# IO4-SignalDriver-Small.net
KiCad netlist of a schematic drawn in EAGLE
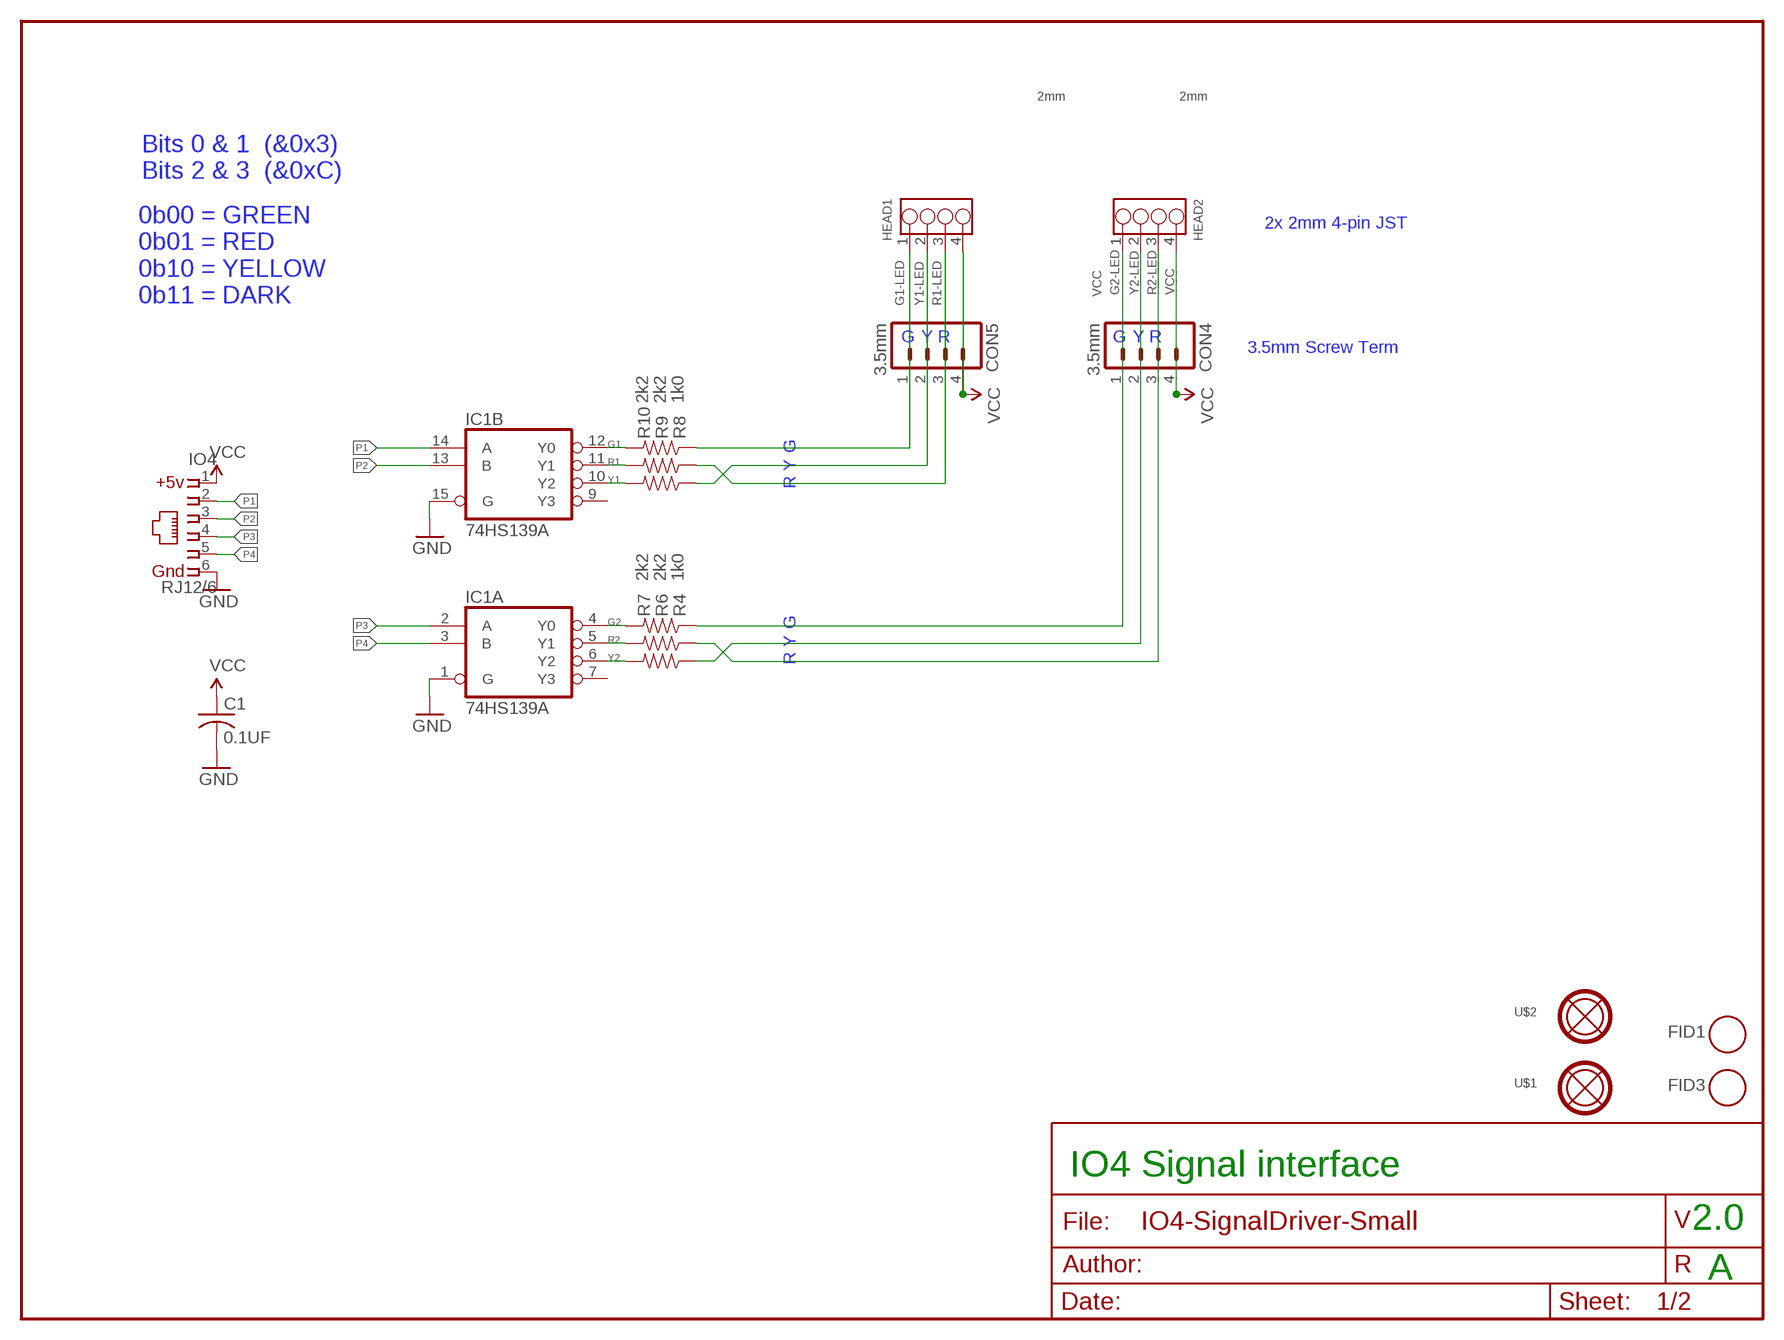
[diagram p0: schematic, sheet 1]
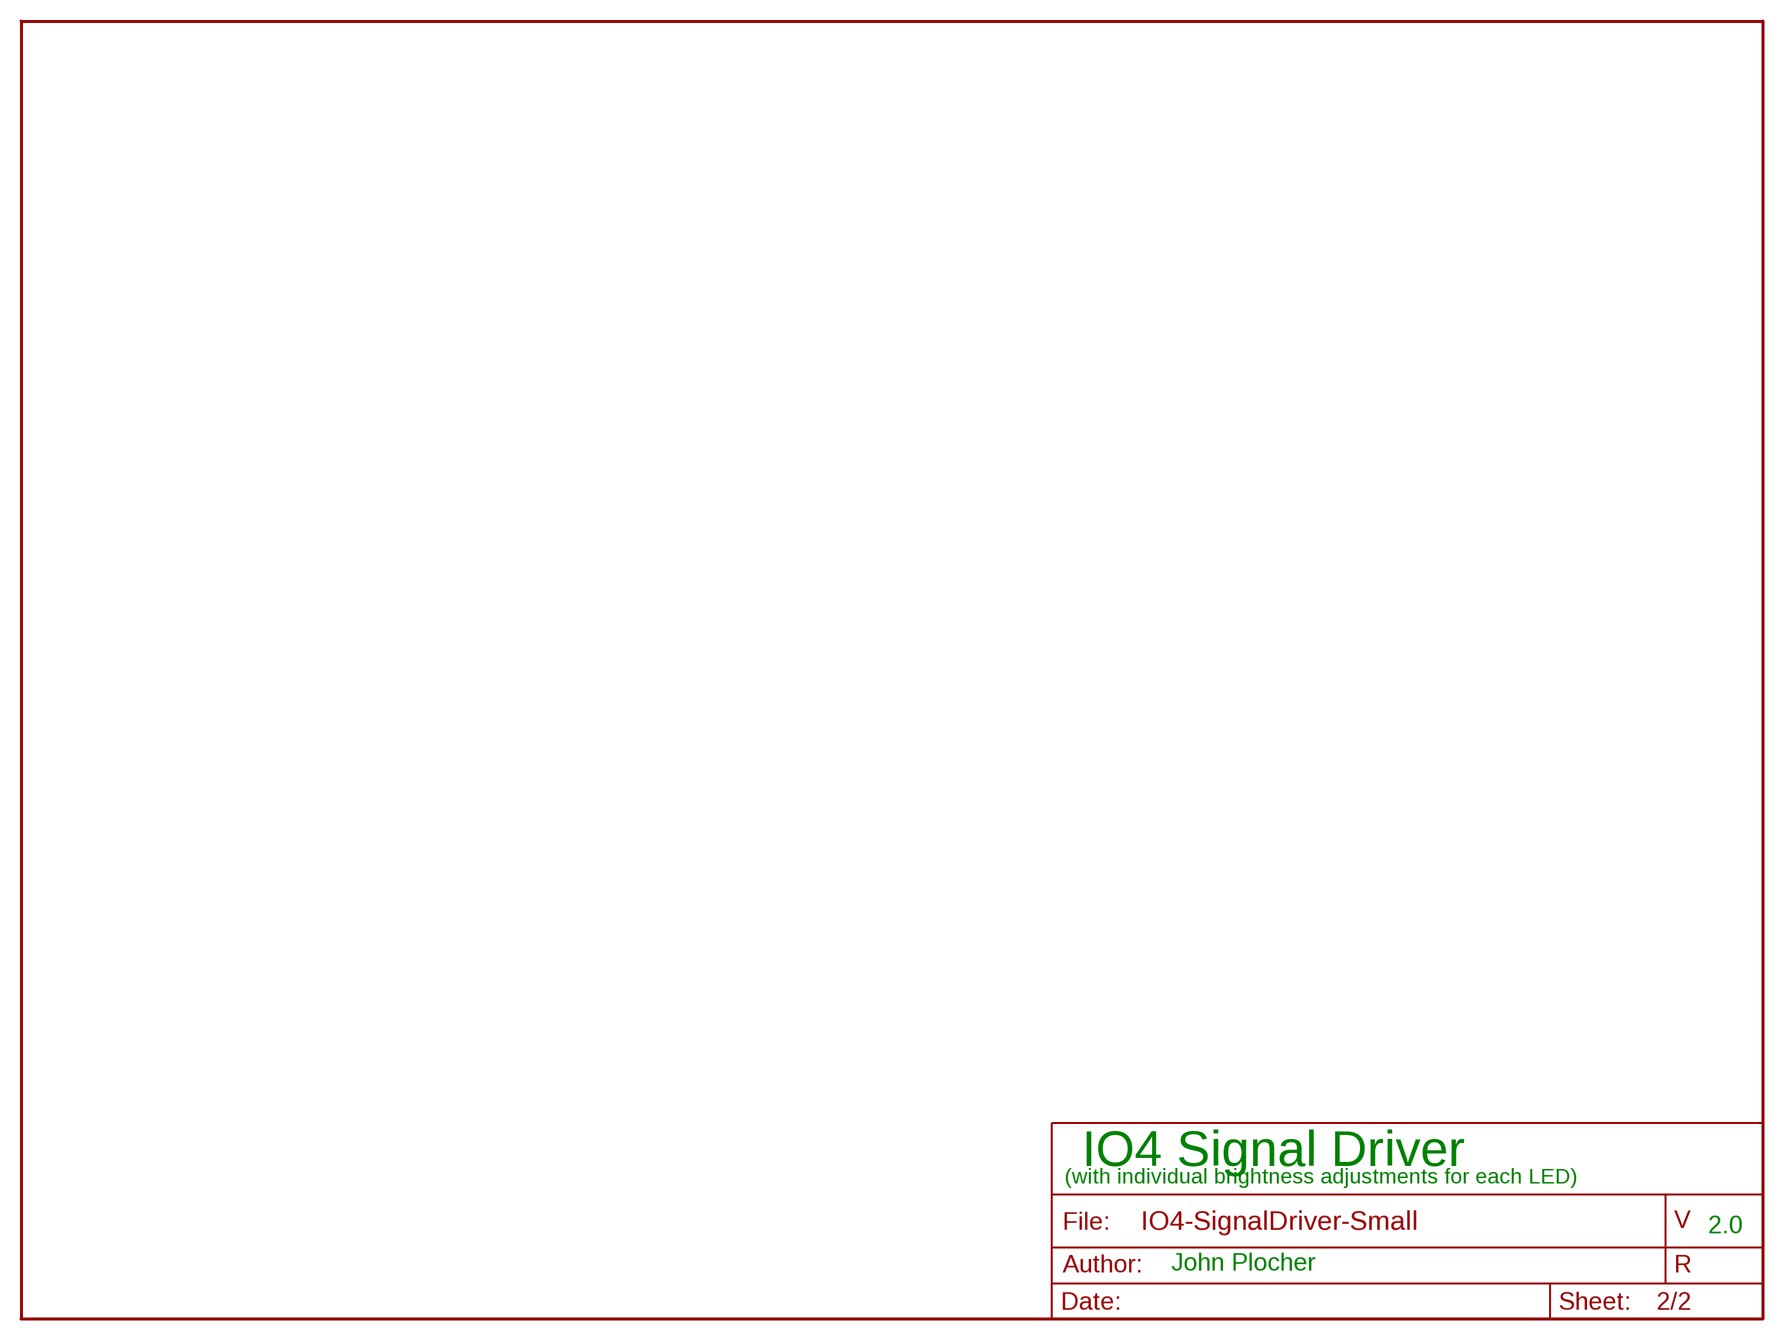
[diagram p1: schematic, sheet 2]

(export (version "E")
  (design (tool "Eeschema 10.0.6"))
  (components
    (comp (ref "C1")
      (value "0.1UF")
      (footprint "eagle-import:0603-CAP")
      (libsource (lib "eagle-import") (part "CAP0603"))
    )
    (comp (ref "CON4")
      (value "3.5mm")
      (footprint "eagle-import:SCREWTERMINAL-3.5MM-4")
      (libsource (lib "eagle-import") (part "CONNECTOR-M04SCREW"))
    )
    (comp (ref "CON5")
      (value "3.5mm")
      (footprint "eagle-import:SCREWTERMINAL-3.5MM-4")
      (libsource (lib "eagle-import") (part "CONNECTOR-M04SCREW"))
    )
    (comp (ref "FID1")
      (value "FIDUCIAL")
      (footprint "eagle-import:FIDUCIAL_1MM")
      (libsource (lib "eagle-import") (part "FIDUCIAL"))
    )
    (comp (ref "FID3")
      (value "FIDUCIAL")
      (footprint "eagle-import:FIDUCIAL_1MM")
      (libsource (lib "eagle-import") (part "FIDUCIAL"))
    )
    (comp (ref "HEAD1")
      (value "2mm")
      (footprint "eagle-import:4P-2.0")
      (libsource (lib "eagle-import") (part "CONNECTOR-GROVE-4P-2.0-3470130P1"))
    )
    (comp (ref "HEAD2")
      (value "2mm")
      (footprint "eagle-import:4P-2.0")
      (libsource (lib "eagle-import") (part "CONNECTOR-GROVE-4P-2.0-3470130P1"))
    )
    (comp (ref "IC1")
      (value "74HS139A")
      (footprint "eagle-import:SO16")
      (libsource (lib "eagle-import") (part "74139DLS"))
    )
    (comp (ref "IO4")
      (value "RJ12/6")
      (footprint "eagle-import:RJ25-INVERTED")
      (libsource (lib "eagle-import") (part "CONNECTOR-IO4INV"))
    )
    (comp (ref "R4")
      (value "1k0")
      (footprint "eagle-import:0603-RES")
      (libsource (lib "eagle-import") (part "R0603-RES"))
    )
    (comp (ref "R6")
      (value "2k2")
      (footprint "eagle-import:0603-RES")
      (libsource (lib "eagle-import") (part "R0603-RES"))
    )
    (comp (ref "R7")
      (value "2k2")
      (footprint "eagle-import:0603-RES")
      (libsource (lib "eagle-import") (part "R0603-RES"))
    )
    (comp (ref "R8")
      (value "1k0")
      (footprint "eagle-import:0603-RES")
      (libsource (lib "eagle-import") (part "R0603-RES"))
    )
    (comp (ref "R9")
      (value "2k2")
      (footprint "eagle-import:0603-RES")
      (libsource (lib "eagle-import") (part "R0603-RES"))
    )
    (comp (ref "R10")
      (value "2k2")
      (footprint "eagle-import:0603-RES")
      (libsource (lib "eagle-import") (part "R0603-RES"))
    )
    (comp (ref "U$1")
      (value "MOUNTINGHOLE")
      (footprint "eagle-import:MOUNTINGHOLE")
      (libsource (lib "eagle-import") (part "MOUNTINGHOLE"))
    )
    (comp (ref "U$2")
      (value "MOUNTINGHOLE")
      (footprint "eagle-import:MOUNTINGHOLE")
      (libsource (lib "eagle-import") (part "MOUNTINGHOLE"))
    )
  )
  (nets
    (net (code "1") (name "G1") (class "Default")
      (node (ref "IC1") (pin "12") (pinfunction "Y0_12") (pintype "output"))
      (node (ref "R10") (pin "2") (pinfunction "2_2") (pintype "passive"))
    )
    (net (code "2") (name "G1-LED") (class "Default")
      (node (ref "CON5") (pin "1") (pinfunction "1_1") (pintype "passive"))
      (node (ref "HEAD1") (pin "1") (pinfunction "1_1") (pintype "bidirectional"))
      (node (ref "R10") (pin "1") (pinfunction "1_1") (pintype "passive"))
    )
    (net (code "3") (name "G2") (class "Default")
      (node (ref "IC1") (pin "4") (pinfunction "Y0_4") (pintype "output"))
      (node (ref "R7") (pin "2") (pinfunction "2_2") (pintype "passive"))
    )
    (net (code "4") (name "G2-LED") (class "Default")
      (node (ref "CON4") (pin "1") (pinfunction "1_1") (pintype "passive"))
      (node (ref "HEAD2") (pin "1") (pinfunction "1_1") (pintype "bidirectional"))
      (node (ref "R7") (pin "1") (pinfunction "1_1") (pintype "passive"))
    )
    (net (code "5") (name "GND") (class "Default")
      (node (ref "C1") (pin "2") (pinfunction "2_2") (pintype "passive"))
      (node (ref "IC1") (pin "1") (pinfunction "G_1") (pintype "input"))
      (node (ref "IC1") (pin "15") (pinfunction "G_15") (pintype "input"))
      (node (ref "IO4") (pin "6") (pinfunction "6_6") (pintype "power_in"))
    )
    (net (code "6") (name "P1") (class "Default")
      (node (ref "IC1") (pin "14") (pinfunction "A_14") (pintype "input"))
      (node (ref "IO4") (pin "2") (pinfunction "2_2") (pintype "passive"))
    )
    (net (code "7") (name "P2") (class "Default")
      (node (ref "IC1") (pin "13") (pinfunction "B_13") (pintype "input"))
      (node (ref "IO4") (pin "3") (pinfunction "3_3") (pintype "passive"))
    )
    (net (code "8") (name "P3") (class "Default")
      (node (ref "IC1") (pin "2") (pinfunction "A_2") (pintype "input"))
      (node (ref "IO4") (pin "4") (pinfunction "4_4") (pintype "passive"))
    )
    (net (code "9") (name "P4") (class "Default")
      (node (ref "IC1") (pin "3") (pinfunction "B_3") (pintype "input"))
      (node (ref "IO4") (pin "5") (pinfunction "5_5") (pintype "passive"))
    )
    (net (code "10") (name "R1") (class "Default")
      (node (ref "IC1") (pin "11") (pinfunction "Y1_11") (pintype "output"))
      (node (ref "R9") (pin "2") (pinfunction "2_2") (pintype "passive"))
    )
    (net (code "11") (name "R1-LED") (class "Default")
      (node (ref "CON5") (pin "3") (pinfunction "3_3") (pintype "passive"))
      (node (ref "HEAD1") (pin "3") (pinfunction "3_3") (pintype "bidirectional"))
      (node (ref "R9") (pin "1") (pinfunction "1_1") (pintype "passive"))
    )
    (net (code "12") (name "R2") (class "Default")
      (node (ref "IC1") (pin "5") (pinfunction "Y1_5") (pintype "output"))
      (node (ref "R6") (pin "2") (pinfunction "2_2") (pintype "passive"))
    )
    (net (code "13") (name "R2-LED") (class "Default")
      (node (ref "CON4") (pin "3") (pinfunction "3_3") (pintype "passive"))
      (node (ref "HEAD2") (pin "3") (pinfunction "3_3") (pintype "bidirectional"))
      (node (ref "R6") (pin "1") (pinfunction "1_1") (pintype "passive"))
    )
    (net (code "14") (name "VCC") (class "Default")
      (node (ref "C1") (pin "1") (pinfunction "1_1") (pintype "passive"))
      (node (ref "CON4") (pin "4") (pinfunction "4_4") (pintype "passive"))
      (node (ref "CON5") (pin "4") (pinfunction "4_4") (pintype "passive"))
      (node (ref "HEAD1") (pin "4") (pinfunction "4_4") (pintype "bidirectional"))
      (node (ref "HEAD2") (pin "4") (pinfunction "4_4") (pintype "bidirectional"))
      (node (ref "IO4") (pin "1") (pinfunction "1_1") (pintype "power_in"))
    )
    (net (code "15") (name "Y1") (class "Default")
      (node (ref "IC1") (pin "10") (pinfunction "Y2_10") (pintype "output"))
      (node (ref "R8") (pin "2") (pinfunction "2_2") (pintype "passive"))
    )
    (net (code "16") (name "Y1-LED") (class "Default")
      (node (ref "CON5") (pin "2") (pinfunction "2_2") (pintype "passive"))
      (node (ref "HEAD1") (pin "2") (pinfunction "2_2") (pintype "bidirectional"))
      (node (ref "R8") (pin "1") (pinfunction "1_1") (pintype "passive"))
    )
    (net (code "17") (name "Y2") (class "Default")
      (node (ref "IC1") (pin "6") (pinfunction "Y2_6") (pintype "output"))
      (node (ref "R4") (pin "2") (pinfunction "2_2") (pintype "passive"))
    )
    (net (code "18") (name "Y2-LED") (class "Default")
      (node (ref "CON4") (pin "2") (pinfunction "2_2") (pintype "passive"))
      (node (ref "HEAD2") (pin "2") (pinfunction "2_2") (pintype "bidirectional"))
      (node (ref "R4") (pin "1") (pinfunction "1_1") (pintype "passive"))
    )
    (net (code "19") (name "unconnected-(IC1A-Y3-Pad7)") (class "Default")
      (node (ref "IC1") (pin "7") (pinfunction "Y3_7") (pintype "output"))
    )
    (net (code "20") (name "unconnected-(IC1B-Y3-Pad9)") (class "Default")
      (node (ref "IC1") (pin "9") (pinfunction "Y3_9") (pintype "output"))
    )
  )
)
